# Main_sheet.net
KiCad netlist of a schematic drawn in Altium Designer
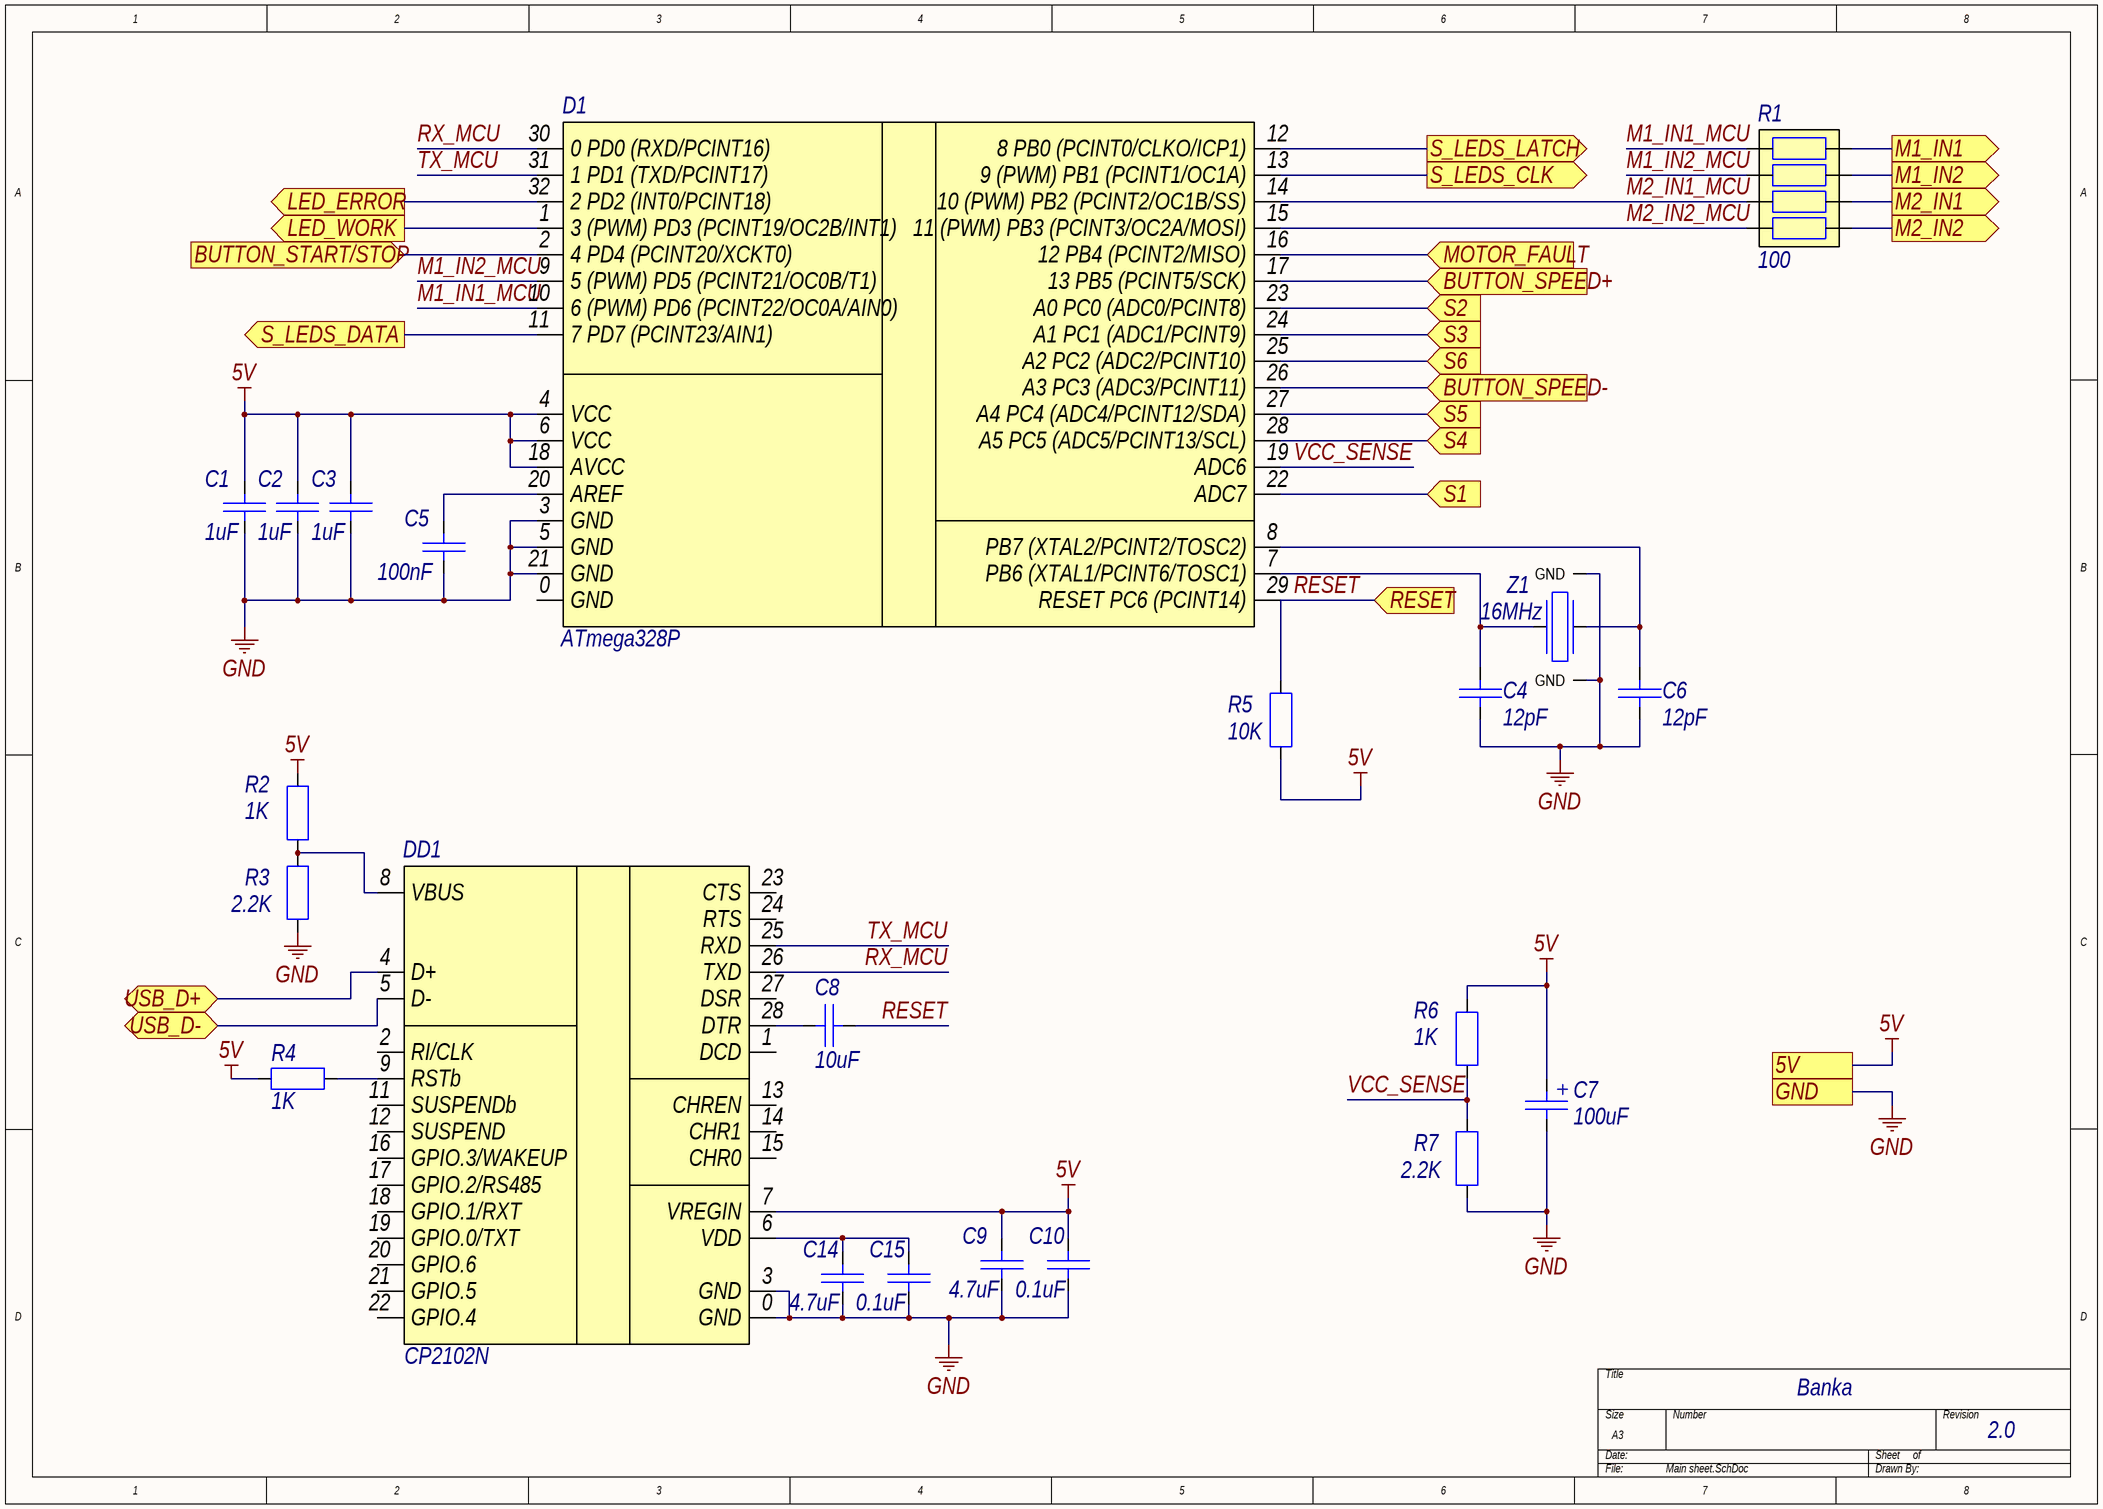
[diagram p0: Main sheet.SchDoc]

(export (version "E")
  (design (tool "Eeschema 10.0.6"))
  (components
    (comp (ref "C1")
      (value "1uF")
      (footprint "Footprints:NPC0805")
      (description "Nonpolarized Capacitor (Ceramic)")
      (libsource (lib "Passive") (part "Nonpolarized Capacitor"))
    )
    (comp (ref "C2")
      (value "1uF")
      (footprint "Footprints:NPC0805")
      (description "Nonpolarized Capacitor (Ceramic)")
      (libsource (lib "Passive") (part "Nonpolarized Capacitor"))
    )
    (comp (ref "C3")
      (value "1uF")
      (footprint "Footprints:NPC0805")
      (description "Nonpolarized Capacitor (Ceramic)")
      (libsource (lib "Passive") (part "Nonpolarized Capacitor"))
    )
    (comp (ref "C4")
      (value "12pF")
      (footprint "Footprints:NPC0805")
      (description "Nonpolarized Capacitor (Ceramic)")
      (libsource (lib "Passive") (part "Nonpolarized Capacitor"))
    )
    (comp (ref "C5")
      (value "100nF")
      (footprint "Footprints:NPC0805")
      (description "Nonpolarized Capacitor (Ceramic)")
      (libsource (lib "Passive") (part "Nonpolarized Capacitor"))
    )
    (comp (ref "C6")
      (value "12pF")
      (footprint "Footprints:NPC0805")
      (description "Nonpolarized Capacitor (Ceramic)")
      (libsource (lib "Passive") (part "Nonpolarized Capacitor"))
    )
    (comp (ref "C7")
      (value "100uF")
      (footprint "Footprints:TANTAL CAPACITOR C")
      (description "Polarized Capacitor (Electrolytic, tantalum)")
      (libsource (lib "Passive") (part "Polarized Capacitor"))
    )
    (comp (ref "C8")
      (value "10uF")
      (footprint "Footprints:NPC0805")
      (description "Nonpolarized Capacitor (Ceramic)")
      (libsource (lib "Passive") (part "Nonpolarized Capacitor"))
    )
    (comp (ref "C9")
      (value "4.7uF")
      (footprint "Footprints:NPC0805")
      (description "Nonpolarized Capacitor (Ceramic)")
      (libsource (lib "Passive") (part "Nonpolarized Capacitor"))
    )
    (comp (ref "C10")
      (value "0.1uF")
      (footprint "Footprints:NPC0805")
      (description "Nonpolarized Capacitor (Ceramic)")
      (libsource (lib "Passive") (part "Nonpolarized Capacitor"))
    )
    (comp (ref "C14")
      (value "4.7uF")
      (footprint "Footprints:NPC0805")
      (description "Nonpolarized Capacitor (Ceramic)")
      (libsource (lib "Passive") (part "Nonpolarized Capacitor"))
    )
    (comp (ref "C15")
      (value "0.1uF")
      (footprint "Footprints:NPC0805")
      (description "Nonpolarized Capacitor (Ceramic)")
      (libsource (lib "Passive") (part "Nonpolarized Capacitor"))
    )
    (comp (ref "D1")
      (value "ATmega328P")
      (footprint "Footprints:TQFP32")
      (description "AVR, 8-bit MCU, 20MHz, 32KB Flash")
      (libsource (lib "Microcontrollers") (part "ATmega328P"))
    )
    (comp (ref "DD1")
      (value "CP2102N")
      (footprint "Footprints:QFN28 (5x5)")
      (description "USB-UART converter")
      (libsource (lib "Miscellaneous") (part "CP2102N 28 pin"))
    )
    (comp (ref "R1")
      (value "100")
      (footprint "Footprints:CAT16")
      (description "Resistor Array")
      (libsource (lib "Passive") (part "Resistor Array"))
    )
    (comp (ref "R2")
      (value "1K")
      (footprint "Footprints:R0805")
      (description "Resistor")
      (libsource (lib "Passive") (part "Resistor"))
    )
    (comp (ref "R3")
      (value "2.2K")
      (footprint "Footprints:R0805")
      (description "Resistor")
      (libsource (lib "Passive") (part "Resistor"))
    )
    (comp (ref "R4")
      (value "1K")
      (footprint "Footprints:R0805")
      (description "Resistor")
      (libsource (lib "") (part "Resistor_1"))
    )
    (comp (ref "R5")
      (value "10K")
      (footprint "Footprints:R0805")
      (description "Resistor")
      (libsource (lib "Passive") (part "Resistor"))
    )
    (comp (ref "R6")
      (value "1K")
      (footprint "Footprints:R0805")
      (description "Resistor")
      (libsource (lib "Passive") (part "Resistor"))
    )
    (comp (ref "R7")
      (value "2.2K")
      (footprint "Footprints:R0805")
      (description "Resistor")
      (libsource (lib "Passive") (part "Resistor"))
    )
    (comp (ref "Z1")
      (value "16MHz")
      (footprint "Footprints:KX-7T")
      (description "Quartz oscillator")
      (fields (field (name "MANUFACTURER") "Geyer Electronics") (field (name "TOLERANCE") "30ppm"))
      (libsource (lib "Passive") (part "Quartz Crystal"))
    )
  )
  (nets
    (net (code "2") (name "/BUTTON_SPEED+") (class "Default")
      (node (ref "D1") (pin "17") (pinfunction "13_PB5_(PCINT5/SCK)_17") (pintype "passive"))
    )
    (net (code "3") (name "/BUTTON_SPEED-") (class "Default")
      (node (ref "D1") (pin "26") (pinfunction "A3_PC3_(ADC3/PCINT11)_26") (pintype "passive"))
    )
    (net (code "4") (name "/BUTTON_START{slash}STOP") (class "Default")
      (node (ref "D1") (pin "2") (pinfunction "4_PD4_(PCINT20/XCKT0)_2") (pintype "passive"))
    )
    (net (code "5") (name "/LED_ERROR") (class "Default")
      (node (ref "D1") (pin "32") (pinfunction "2_PD2_(INT0/PCINT18)_32") (pintype "passive"))
    )
    (net (code "6") (name "/LED_WORK") (class "Default")
      (node (ref "D1") (pin "1") (pinfunction "3_(PWM)_PD3_(PCINT19/OC2B/INT1)_1") (pintype "passive"))
    )
    (net (code "7") (name "/M1_IN1") (class "Default")
      (node (ref "R1") (pin "4") (pinfunction "4_4") (pintype "passive"))
    )
    (net (code "8") (name "/M1_IN1_MCU") (class "Default")
      (node (ref "D1") (pin "10") (pinfunction "6_(PWM)_PD6_(PCINT22/OC0A/AIN0)_10") (pintype "passive"))
      (node (ref "R1") (pin "5") (pinfunction "5_5") (pintype "passive"))
    )
    (net (code "9") (name "/M1_IN2") (class "Default")
      (node (ref "R1") (pin "3") (pinfunction "3_3") (pintype "passive"))
    )
    (net (code "10") (name "/M1_IN2_MCU") (class "Default")
      (node (ref "D1") (pin "9") (pinfunction "5_(PWM)_PD5_(PCINT21/OC0B/T1)_9") (pintype "passive"))
      (node (ref "R1") (pin "6") (pinfunction "6_6") (pintype "passive"))
    )
    (net (code "11") (name "/M2_IN1") (class "Default")
      (node (ref "R1") (pin "2") (pinfunction "2_2") (pintype "passive"))
    )
    (net (code "12") (name "/M2_IN1_MCU") (class "Default")
      (node (ref "D1") (pin "14") (pinfunction "10_(PWM)_PB2_(PCINT2/OC1B/SS)_14") (pintype "passive"))
      (node (ref "R1") (pin "7") (pinfunction "7_7") (pintype "passive"))
    )
    (net (code "13") (name "/M2_IN2") (class "Default")
      (node (ref "R1") (pin "1") (pinfunction "1_1") (pintype "passive"))
    )
    (net (code "14") (name "/M2_IN2_MCU") (class "Default")
      (node (ref "D1") (pin "15") (pinfunction "11_(PWM)_PB3_(PCINT3/OC2A/MOSI)_15") (pintype "passive"))
      (node (ref "R1") (pin "8") (pinfunction "8_8") (pintype "passive"))
    )
    (net (code "15") (name "/MOTOR_FAULT") (class "Default")
      (node (ref "D1") (pin "16") (pinfunction "12_PB4_(PCINT2/MISO)_16") (pintype "passive"))
    )
    (net (code "16") (name "/RESET") (class "Default")
      (node (ref "C8") (pin "1") (pinfunction "1_1") (pintype "passive"))
      (node (ref "D1") (pin "29") (pinfunction "RESET_PC6_(PCINT14)_29") (pintype "passive"))
      (node (ref "R5") (pin "2") (pinfunction "2_2") (pintype "passive"))
    )
    (net (code "17") (name "/RX_MCU") (class "Default")
      (node (ref "D1") (pin "30") (pinfunction "0_PD0_(RXD/PCINT16)_30") (pintype "passive"))
      (node (ref "DD1") (pin "26") (pinfunction "TXD_26") (pintype "passive"))
    )
    (net (code "18") (name "/S1") (class "Default")
      (node (ref "D1") (pin "22") (pinfunction "ADC7_22") (pintype "passive"))
    )
    (net (code "19") (name "/S2") (class "Default")
      (node (ref "D1") (pin "23") (pinfunction "A0_PC0_(ADC0/PCINT8)_23") (pintype "passive"))
    )
    (net (code "20") (name "/S3") (class "Default")
      (node (ref "D1") (pin "24") (pinfunction "A1_PC1_(ADC1/PCINT9)_24") (pintype "passive"))
    )
    (net (code "21") (name "/S4") (class "Default")
      (node (ref "D1") (pin "28") (pinfunction "A5_PC5_(ADC5/PCINT13/SCL)_28") (pintype "passive"))
    )
    (net (code "22") (name "/S5") (class "Default")
      (node (ref "D1") (pin "27") (pinfunction "A4_PC4_(ADC4/PCINT12/SDA)_27") (pintype "passive"))
    )
    (net (code "23") (name "/S6") (class "Default")
      (node (ref "D1") (pin "25") (pinfunction "A2_PC2_(ADC2/PCINT10)_25") (pintype "passive"))
    )
    (net (code "24") (name "/S_LEDS_CLK") (class "Default")
      (node (ref "D1") (pin "13") (pinfunction "9_(PWM)_PB1_(PCINT1/OC1A)_13") (pintype "passive"))
    )
    (net (code "25") (name "/S_LEDS_DATA") (class "Default")
      (node (ref "D1") (pin "11") (pinfunction "7_PD7_(PCINT23/AIN1)_11") (pintype "passive"))
    )
    (net (code "26") (name "/S_LEDS_LATCH") (class "Default")
      (node (ref "D1") (pin "12") (pinfunction "8_PB0_(PCINT0/CLKO/ICP1)_12") (pintype "passive"))
    )
    (net (code "27") (name "/TX_MCU") (class "Default")
      (node (ref "D1") (pin "31") (pinfunction "1_PD1_(TXD/PCINT17)_31") (pintype "passive"))
      (node (ref "DD1") (pin "25") (pinfunction "RXD_25") (pintype "passive"))
    )
    (net (code "28") (name "/USB_D+") (class "Default")
      (node (ref "DD1") (pin "4") (pinfunction "D+_4") (pintype "passive"))
    )
    (net (code "29") (name "/USB_D-") (class "Default")
      (node (ref "DD1") (pin "5") (pinfunction "D-_5") (pintype "passive"))
    )
    (net (code "30") (name "/VCC_SENSE") (class "Default")
      (node (ref "D1") (pin "19") (pinfunction "ADC6_19") (pintype "passive"))
      (node (ref "R6") (pin "1") (pinfunction "1_1") (pintype "passive"))
      (node (ref "R7") (pin "2") (pinfunction "2_2") (pintype "passive"))
    )
    (net (code "31") (name "5V") (class "Default")
      (node (ref "C1") (pin "2") (pinfunction "2_2") (pintype "passive"))
      (node (ref "C10") (pin "2") (pinfunction "2_2") (pintype "passive"))
      (node (ref "C2") (pin "2") (pinfunction "2_2") (pintype "passive"))
      (node (ref "C3") (pin "2") (pinfunction "2_2") (pintype "passive"))
      (node (ref "C7") (pin "1") (pinfunction "1_1") (pintype "passive"))
      (node (ref "C9") (pin "2") (pinfunction "2_2") (pintype "passive"))
      (node (ref "D1") (pin "18") (pinfunction "AVCC_18") (pintype "passive"))
      (node (ref "D1") (pin "4") (pinfunction "VCC_4") (pintype "passive"))
      (node (ref "D1") (pin "6") (pinfunction "VCC_6") (pintype "passive"))
      (node (ref "DD1") (pin "7") (pinfunction "VREGIN_7") (pintype "passive"))
      (node (ref "R2") (pin "2") (pinfunction "2_2") (pintype "passive"))
      (node (ref "R4") (pin "2") (pinfunction "2_2") (pintype "passive"))
      (node (ref "R5") (pin "1") (pinfunction "1_1") (pintype "passive"))
      (node (ref "R6") (pin "2") (pinfunction "2_2") (pintype "passive"))
    )
    (net (code "32") (name "GND") (class "Default")
      (node (ref "C1") (pin "1") (pinfunction "1_1") (pintype "passive"))
      (node (ref "C10") (pin "1") (pinfunction "1_1") (pintype "passive"))
      (node (ref "C14") (pin "1") (pinfunction "1_1") (pintype "passive"))
      (node (ref "C15") (pin "1") (pinfunction "1_1") (pintype "passive"))
      (node (ref "C2") (pin "1") (pinfunction "1_1") (pintype "passive"))
      (node (ref "C3") (pin "1") (pinfunction "1_1") (pintype "passive"))
      (node (ref "C4") (pin "1") (pinfunction "1_1") (pintype "passive"))
      (node (ref "C5") (pin "1") (pinfunction "1_1") (pintype "passive"))
      (node (ref "C6") (pin "1") (pinfunction "1_1") (pintype "passive"))
      (node (ref "C7") (pin "2") (pinfunction "2_2") (pintype "passive"))
      (node (ref "C9") (pin "1") (pinfunction "1_1") (pintype "passive"))
      (node (ref "D1") (pin "21") (pinfunction "GND_21") (pintype "passive"))
      (node (ref "D1") (pin "3") (pinfunction "GND_3") (pintype "passive"))
      (node (ref "D1") (pin "5") (pinfunction "GND_5") (pintype "passive"))
      (node (ref "DD1") (pin "0") (pinfunction "GND_0") (pintype "passive"))
      (node (ref "DD1") (pin "3") (pinfunction "GND_3") (pintype "passive"))
      (node (ref "R3") (pin "1") (pinfunction "1_1") (pintype "passive"))
      (node (ref "R7") (pin "1") (pinfunction "1_1") (pintype "passive"))
      (node (ref "Z1") (pin "3") (pinfunction "GND_3") (pintype "passive"))
      (node (ref "Z1") (pin "4") (pinfunction "GND_4") (pintype "passive"))
    )
    (net (code "33") (name "Net-(D1-AREF)") (class "Default")
      (node (ref "C5") (pin "2") (pinfunction "2_2") (pintype "passive"))
      (node (ref "D1") (pin "20") (pinfunction "AREF_20") (pintype "passive"))
    )
    (net (code "34") (name "Net-(D1-PB6_(XTAL1{slash}PCINT6{slash}TOSC1))") (class "Default")
      (node (ref "C4") (pin "2") (pinfunction "2_2") (pintype "passive"))
      (node (ref "D1") (pin "7") (pinfunction "PB6_(XTAL1/PCINT6/TOSC1)_7") (pintype "passive"))
      (node (ref "Z1") (pin "1") (pinfunction "1_1") (pintype "passive"))
    )
    (net (code "35") (name "Net-(D1-PB7_(XTAL2{slash}PCINT2{slash}TOSC2))") (class "Default")
      (node (ref "C6") (pin "2") (pinfunction "2_2") (pintype "passive"))
      (node (ref "D1") (pin "8") (pinfunction "PB7_(XTAL2/PCINT2/TOSC2)_8") (pintype "passive"))
      (node (ref "Z1") (pin "2") (pinfunction "2_2") (pintype "passive"))
    )
    (net (code "36") (name "Net-(DD1-DTR)") (class "Default")
      (node (ref "C8") (pin "2") (pinfunction "2_2") (pintype "passive"))
      (node (ref "DD1") (pin "28") (pinfunction "DTR_28") (pintype "passive"))
    )
    (net (code "37") (name "Net-(DD1-RSTb)") (class "Default")
      (node (ref "DD1") (pin "9") (pinfunction "RSTb_9") (pintype "passive"))
      (node (ref "R4") (pin "1") (pinfunction "1_1") (pintype "passive"))
    )
    (net (code "38") (name "Net-(DD1-VBUS)") (class "Default")
      (node (ref "DD1") (pin "8") (pinfunction "VBUS_8") (pintype "passive"))
      (node (ref "R2") (pin "1") (pinfunction "1_1") (pintype "passive"))
      (node (ref "R3") (pin "2") (pinfunction "2_2") (pintype "passive"))
    )
    (net (code "39") (name "Net-(DD1-VDD)") (class "Default")
      (node (ref "C14") (pin "2") (pinfunction "2_2") (pintype "passive"))
      (node (ref "C15") (pin "2") (pinfunction "2_2") (pintype "passive"))
      (node (ref "DD1") (pin "6") (pinfunction "VDD_6") (pintype "passive"))
    )
    (net (code "40") (name "unconnected-(D1-GND-Pad0)") (class "Default")
      (node (ref "D1") (pin "0") (pinfunction "GND_0") (pintype "passive"))
    )
    (net (code "41") (name "unconnected-(DD1-CHR0-Pad15)") (class "Default")
      (node (ref "DD1") (pin "15") (pinfunction "CHR0_15") (pintype "passive"))
    )
    (net (code "42") (name "unconnected-(DD1-CHR1-Pad14)") (class "Default")
      (node (ref "DD1") (pin "14") (pinfunction "CHR1_14") (pintype "passive"))
    )
    (net (code "43") (name "unconnected-(DD1-CHREN-Pad13)") (class "Default")
      (node (ref "DD1") (pin "13") (pinfunction "CHREN_13") (pintype "passive"))
    )
    (net (code "44") (name "unconnected-(DD1-CTS-Pad23)") (class "Default")
      (node (ref "DD1") (pin "23") (pinfunction "CTS_23") (pintype "passive"))
    )
    (net (code "45") (name "unconnected-(DD1-DCD-Pad1)") (class "Default")
      (node (ref "DD1") (pin "1") (pinfunction "DCD_1") (pintype "passive"))
    )
    (net (code "46") (name "unconnected-(DD1-DSR-Pad27)") (class "Default")
      (node (ref "DD1") (pin "27") (pinfunction "DSR_27") (pintype "passive"))
    )
    (net (code "47") (name "unconnected-(DD1-GPIO.0{slash}TXT-Pad19)") (class "Default")
      (node (ref "DD1") (pin "19") (pinfunction "GPIO.0/TXT_19") (pintype "passive"))
    )
    (net (code "48") (name "unconnected-(DD1-GPIO.1{slash}RXT-Pad18)") (class "Default")
      (node (ref "DD1") (pin "18") (pinfunction "GPIO.1/RXT_18") (pintype "passive"))
    )
    (net (code "49") (name "unconnected-(DD1-GPIO.2{slash}RS485-Pad17)") (class "Default")
      (node (ref "DD1") (pin "17") (pinfunction "GPIO.2/RS485_17") (pintype "passive"))
    )
    (net (code "50") (name "unconnected-(DD1-GPIO.3{slash}WAKEUP-Pad16)") (class "Default")
      (node (ref "DD1") (pin "16") (pinfunction "GPIO.3/WAKEUP_16") (pintype "passive"))
    )
    (net (code "51") (name "unconnected-(DD1-GPIO.4-Pad22)") (class "Default")
      (node (ref "DD1") (pin "22") (pinfunction "GPIO.4_22") (pintype "passive"))
    )
    (net (code "52") (name "unconnected-(DD1-GPIO.5-Pad21)") (class "Default")
      (node (ref "DD1") (pin "21") (pinfunction "GPIO.5_21") (pintype "passive"))
    )
    (net (code "53") (name "unconnected-(DD1-GPIO.6-Pad20)") (class "Default")
      (node (ref "DD1") (pin "20") (pinfunction "GPIO.6_20") (pintype "passive"))
    )
    (net (code "54") (name "unconnected-(DD1-RI{slash}CLK-Pad2)") (class "Default")
      (node (ref "DD1") (pin "2") (pinfunction "RI/CLK_2") (pintype "passive"))
    )
    (net (code "55") (name "unconnected-(DD1-RTS-Pad24)") (class "Default")
      (node (ref "DD1") (pin "24") (pinfunction "RTS_24") (pintype "passive"))
    )
    (net (code "56") (name "unconnected-(DD1-SUSPEND-Pad12)") (class "Default")
      (node (ref "DD1") (pin "12") (pinfunction "SUSPEND_12") (pintype "passive"))
    )
    (net (code "57") (name "unconnected-(DD1-SUSPENDb-Pad11)") (class "Default")
      (node (ref "DD1") (pin "11") (pinfunction "SUSPENDb_11") (pintype "passive"))
    )
  )
)
